# Radarv3.net
KiCad netlist of a schematic drawn in EAGLE
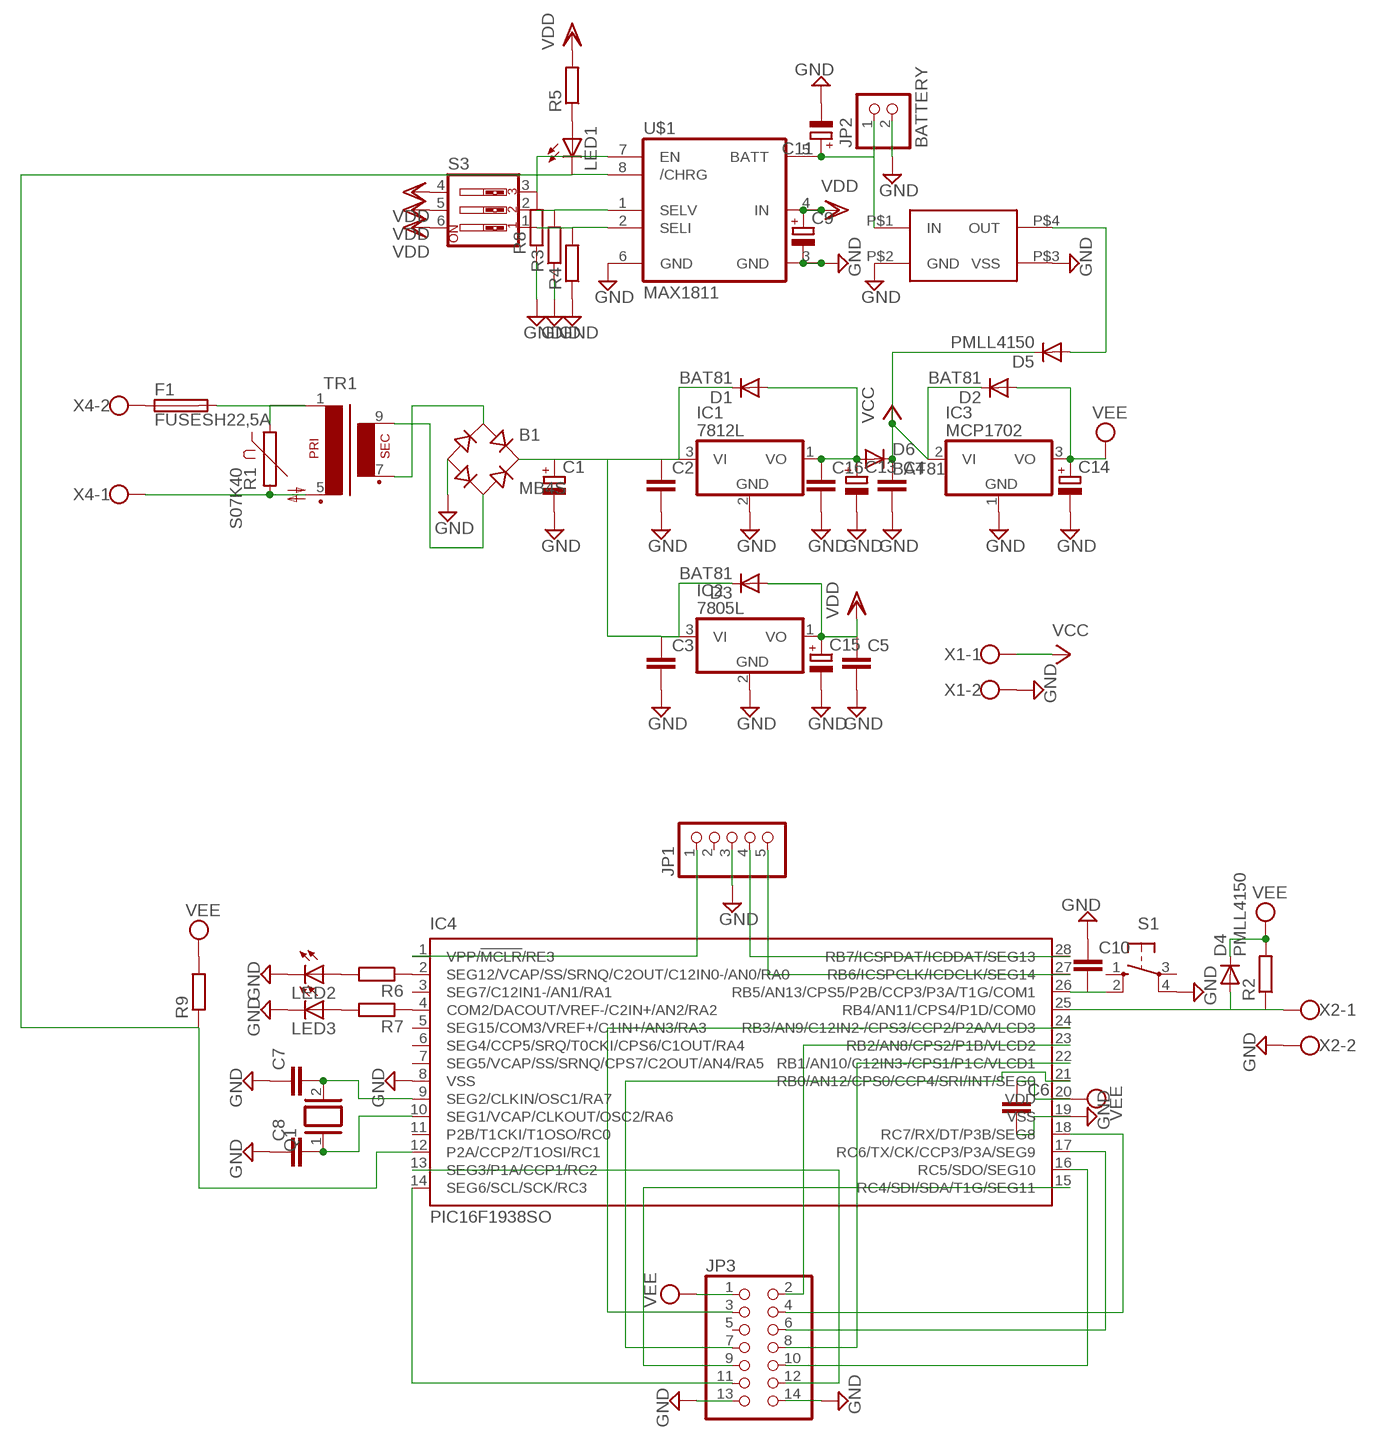
[diagram p0: schematic, sheet 1]

(export (version "E")
  (design (tool "Eeschema 10.0.6"))
  (components
    (comp (ref "B1")
      (value "MB4S")
      (footprint "eagle-import:SOIC-4")
      (libsource (lib "eagle-import") (part "MBS4"))
    )
    (comp (ref "C1")
      (value "CPOL-EUE3.5-10")
      (footprint "eagle-import:E3,5-10")
      (libsource (lib "eagle-import") (part "CPOL-EUE3.5-10"))
    )
    (comp (ref "C2")
      (value "C-EUC1206")
      (footprint "eagle-import:C1206")
      (libsource (lib "eagle-import") (part "resistor_C-EUC1206"))
    )
    (comp (ref "C3")
      (value "C-EUC1206")
      (footprint "eagle-import:C1206")
      (libsource (lib "eagle-import") (part "resistor_C-EUC1206"))
    )
    (comp (ref "C4")
      (value "C-EUC1206")
      (footprint "eagle-import:C1206")
      (libsource (lib "eagle-import") (part "resistor_C-EUC1206"))
    )
    (comp (ref "C5")
      (value "C-EUC1206")
      (footprint "eagle-import:C1206")
      (libsource (lib "eagle-import") (part "resistor_C-EUC1206"))
    )
    (comp (ref "C6")
      (value "C-EU025-030X050")
      (footprint "eagle-import:C025-030X050")
      (libsource (lib "eagle-import") (part "C-EU025-030X050"))
    )
    (comp (ref "C7")
      (value "C-EUC1206")
      (footprint "eagle-import:C1206")
      (libsource (lib "eagle-import") (part "resistor_C-EUC1206"))
    )
    (comp (ref "C8")
      (value "C-EUC1206")
      (footprint "eagle-import:C1206")
      (libsource (lib "eagle-import") (part "resistor_C-EUC1206"))
    )
    (comp (ref "C9")
      (value "CPOL-EUE2,5-6E")
      (footprint "eagle-import:E2,5-6E")
      (libsource (lib "eagle-import") (part "CPOL-EUE2,5-6E"))
    )
    (comp (ref "C10")
      (value "C-EUC1206")
      (footprint "eagle-import:C1206")
      (libsource (lib "eagle-import") (part "resistor_C-EUC1206"))
    )
    (comp (ref "C11")
      (value "CPOL-EUE2,5-6E")
      (footprint "eagle-import:E2,5-6E")
      (libsource (lib "eagle-import") (part "CPOL-EUE2,5-6E"))
    )
    (comp (ref "C13")
      (value "CPOL-EUE2,5-6E")
      (footprint "eagle-import:E2,5-6E")
      (libsource (lib "eagle-import") (part "CPOL-EUE2,5-6E"))
    )
    (comp (ref "C14")
      (value "CPOL-EUE2,5-6E")
      (footprint "eagle-import:E2,5-6E")
      (libsource (lib "eagle-import") (part "CPOL-EUE2,5-6E"))
    )
    (comp (ref "C15")
      (value "CPOL-EUE2,5-6E")
      (footprint "eagle-import:E2,5-6E")
      (libsource (lib "eagle-import") (part "CPOL-EUE2,5-6E"))
    )
    (comp (ref "C16")
      (value "C-EUC1206")
      (footprint "eagle-import:C1206")
      (libsource (lib "eagle-import") (part "resistor_C-EUC1206"))
    )
    (comp (ref "D1")
      (value "BAT81")
      (footprint "eagle-import:DO34-7")
      (libsource (lib "eagle-import") (part "BAT81"))
    )
    (comp (ref "D2")
      (value "BAT81")
      (footprint "eagle-import:DO34-7")
      (libsource (lib "eagle-import") (part "BAT81"))
    )
    (comp (ref "D3")
      (value "BAT81")
      (footprint "eagle-import:DO34-7")
      (libsource (lib "eagle-import") (part "BAT81"))
    )
    (comp (ref "D4")
      (value "PMLL4150")
      (footprint "eagle-import:SOD80C")
      (libsource (lib "eagle-import") (part "PMLL4150"))
    )
    (comp (ref "D5")
      (value "PMLL4150")
      (footprint "eagle-import:SOD80C")
      (libsource (lib "eagle-import") (part "PMLL4150"))
    )
    (comp (ref "D6")
      (value "BAT81")
      (footprint "eagle-import:DO34-7")
      (libsource (lib "eagle-import") (part "BAT81"))
    )
    (comp (ref "F1")
      (value "FUSESH22,5A")
      (footprint "eagle-import:SH22,5A")
      (libsource (lib "eagle-import") (part "FUSESH22,5A"))
    )
    (comp (ref "IC1")
      (value "7812L")
      (footprint "eagle-import:TO92")
      (libsource (lib "eagle-import") (part "78L12"))
    )
    (comp (ref "IC2")
      (value "7805L")
      (footprint "eagle-import:TO92")
      (libsource (lib "eagle-import") (part "78L05"))
    )
    (comp (ref "IC3")
      (value "MCP1702")
      (footprint "eagle-import:TO-92")
      (libsource (lib "eagle-import") (part "MCP1702"))
    )
    (comp (ref "IC4")
      (value "PIC16F1938SO")
      (footprint "eagle-import:SO28W")
      (fields (field (name "MPN") "PIC16F1938-I/SO"))
      (libsource (lib "eagle-import") (part "PIC16F19SO38"))
    )
    (comp (ref "JP1")
      (value "PINHD-1X5")
      (footprint "eagle-import:1X05")
      (libsource (lib "eagle-import") (part "PINHD-1X5"))
    )
    (comp (ref "JP2")
      (value "BATTERY")
      (footprint "eagle-import:1X02")
      (libsource (lib "eagle-import") (part "PINHD-1X2"))
    )
    (comp (ref "JP3")
      (value "PINHD-2X7")
      (footprint "eagle-import:2X07")
      (libsource (lib "eagle-import") (part "PINHD-2X7"))
    )
    (comp (ref "LED1")
      (value "LED3MM")
      (footprint "eagle-import:LED3MM")
      (libsource (lib "eagle-import") (part "LED3MM"))
    )
    (comp (ref "LED2")
      (value "LED3MM")
      (footprint "eagle-import:LED3MM")
      (libsource (lib "eagle-import") (part "LED3MM"))
    )
    (comp (ref "LED3")
      (value "LED3MM")
      (footprint "eagle-import:LED3MM")
      (libsource (lib "eagle-import") (part "LED3MM"))
    )
    (comp (ref "Q1")
      (value "XTAL/S")
      (footprint "eagle-import:QS")
      (libsource (lib "eagle-import") (part "XTAL/S"))
    )
    (comp (ref "R1")
      (value "S07K40")
      (footprint "eagle-import:S07K40")
      (libsource (lib "eagle-import") (part "S07K40"))
    )
    (comp (ref "R2")
      (value "R-EU_M1206")
      (footprint "eagle-import:M1206")
      (libsource (lib "eagle-import") (part "R-EU_M1206"))
    )
    (comp (ref "R3")
      (value "R-EU_M1206")
      (footprint "eagle-import:M1206")
      (libsource (lib "eagle-import") (part "R-EU_M1206"))
    )
    (comp (ref "R4")
      (value "R-EU_M1206")
      (footprint "eagle-import:M1206")
      (libsource (lib "eagle-import") (part "R-EU_M1206"))
    )
    (comp (ref "R5")
      (value "R-EU_M1206")
      (footprint "eagle-import:M1206")
      (libsource (lib "eagle-import") (part "R-EU_M1206"))
    )
    (comp (ref "R6")
      (value "R-EU_M1206")
      (footprint "eagle-import:M1206")
      (libsource (lib "eagle-import") (part "R-EU_M1206"))
    )
    (comp (ref "R7")
      (value "R-EU_M1206")
      (footprint "eagle-import:M1206")
      (libsource (lib "eagle-import") (part "R-EU_M1206"))
    )
    (comp (ref "R8")
      (value "R-EU_M1206")
      (footprint "eagle-import:M1206")
      (libsource (lib "eagle-import") (part "R-EU_M1206"))
    )
    (comp (ref "R9")
      (value "R-EU_M1206")
      (footprint "eagle-import:M1206")
      (libsource (lib "eagle-import") (part "R-EU_M1206"))
    )
    (comp (ref "S1")
      (value "10-XX")
      (footprint "eagle-import:B3F-10XX")
      (fields (field (name "MPN") "B3F-1000"))
      (libsource (lib "eagle-import") (part "10-XX"))
    )
    (comp (ref "S3")
      (value "SW_DIP-3")
      (footprint "eagle-import:EDG-03")
      (libsource (lib "eagle-import") (part "SW_DIP-3"))
    )
    (comp (ref "TR1")
      (value "VV11")
      (footprint "eagle-import:VV11")
      (libsource (lib "eagle-import") (part "VV11"))
    )
    (comp (ref "U$1")
      (value "MAX1811")
      (footprint "eagle-import:SO08")
      (libsource (lib "eagle-import") (part "MAX1811"))
    )
    (comp (ref "U$2")
      (value "STEP_UP_MODULE")
      (footprint "eagle-import:STEP_UP_MOD")
      (libsource (lib "eagle-import") (part "STEP_UP_MODULE"))
    )
    (comp (ref "X1")
      (value "W237-102")
      (footprint "eagle-import:W237-102")
      (fields
        (field (name "MPN") "237-102")
        (field (name "MPN_1") "237-102")
        (field (name "OC_FARNELL") "unknown")
        (field (name "OC_NEWARK") "70K9898")
      )
      (libsource (lib "eagle-import") (part "W237-102"))
    )
    (comp (ref "X2")
      (value "W237-102")
      (footprint "eagle-import:W237-102")
      (fields
        (field (name "MPN") "237-102")
        (field (name "MPN_1") "237-102")
        (field (name "OC_FARNELL") "unknown")
        (field (name "OC_NEWARK") "70K9898")
      )
      (libsource (lib "eagle-import") (part "W237-102"))
    )
    (comp (ref "X4")
      (value "W237-102")
      (footprint "eagle-import:W237-102")
      (fields
        (field (name "MPN") "237-102")
        (field (name "MPN_1") "237-102")
        (field (name "OC_FARNELL") "unknown")
        (field (name "OC_NEWARK") "70K9898")
      )
      (libsource (lib "eagle-import") (part "W237-102"))
    )
  )
  (nets
    (net (code "1") (name "GND") (class "Default")
      (node (ref "B1") (pin "-") (pinfunction "-_-") (pintype "passive"))
      (node (ref "C1") (pin "-") (pinfunction "-_-") (pintype "passive"))
      (node (ref "C10") (pin "1") (pinfunction "1_1") (pintype "passive"))
      (node (ref "C11") (pin "-") (pinfunction "-_-") (pintype "passive"))
      (node (ref "C13") (pin "-") (pinfunction "-_-") (pintype "passive"))
      (node (ref "C14") (pin "-") (pinfunction "-_-") (pintype "passive"))
      (node (ref "C15") (pin "-") (pinfunction "-_-") (pintype "passive"))
      (node (ref "C16") (pin "2") (pinfunction "2_2") (pintype "passive"))
      (node (ref "C2") (pin "2") (pinfunction "2_2") (pintype "passive"))
      (node (ref "C3") (pin "2") (pinfunction "2_2") (pintype "passive"))
      (node (ref "C4") (pin "2") (pinfunction "2_2") (pintype "passive"))
      (node (ref "C5") (pin "2") (pinfunction "2_2") (pintype "passive"))
      (node (ref "C6") (pin "2") (pinfunction "2_2") (pintype "passive"))
      (node (ref "C7") (pin "1") (pinfunction "1_1") (pintype "passive"))
      (node (ref "C8") (pin "1") (pinfunction "1_1") (pintype "passive"))
      (node (ref "C9") (pin "-") (pinfunction "-_-") (pintype "passive"))
      (node (ref "IC1") (pin "2") (pinfunction "GND_2") (pintype "passive"))
      (node (ref "IC2") (pin "2") (pinfunction "GND_2") (pintype "passive"))
      (node (ref "IC3") (pin "1") (pinfunction "GND_1") (pintype "passive"))
      (node (ref "IC4") (pin "19") (pinfunction "VSS_19") (pintype "power_in"))
      (node (ref "IC4") (pin "8") (pinfunction "VSS_8") (pintype "power_in"))
      (node (ref "JP1") (pin "3") (pinfunction "3_3") (pintype "passive"))
      (node (ref "JP2") (pin "2") (pinfunction "2_2") (pintype "passive"))
      (node (ref "JP3") (pin "13") (pinfunction "13_13") (pintype "passive"))
      (node (ref "JP3") (pin "14") (pinfunction "14_14") (pintype "passive"))
      (node (ref "LED2") (pin "K") (pinfunction "C_K") (pintype "passive"))
      (node (ref "LED3") (pin "K") (pinfunction "C_K") (pintype "passive"))
      (node (ref "R3") (pin "1") (pinfunction "1_1") (pintype "passive"))
      (node (ref "R4") (pin "1") (pinfunction "1_1") (pintype "passive"))
      (node (ref "R8") (pin "1") (pinfunction "1_1") (pintype "passive"))
      (node (ref "S1") (pin "4") (pinfunction "P1_4") (pintype "passive"))
      (node (ref "U$1") (pin "3") (pinfunction "GND_3") (pintype "power_in"))
      (node (ref "U$1") (pin "6") (pinfunction "GND_6") (pintype "power_in"))
      (node (ref "U$2") (pin "P$2") (pinfunction "GND_P$2") (pintype "bidirectional"))
      (node (ref "U$2") (pin "P$3") (pinfunction "VSS_P$3") (pintype "bidirectional"))
      (node (ref "X1") (pin "2") (pinfunction "KL_2") (pintype "passive"))
      (node (ref "X2") (pin "2") (pinfunction "KL_2") (pintype "passive"))
    )
    (net (code "2") (name "Net-(B1-AC1)") (class "Default")
      (node (ref "B1") (pin "~1") (pinfunction "AC1_~1") (pintype "passive"))
      (node (ref "TR1") (pin "7") (pinfunction "S3_7") (pintype "passive"))
    )
    (net (code "3") (name "Net-(B1-AC2)") (class "Default")
      (node (ref "B1") (pin "~2") (pinfunction "AC2_~2") (pintype "passive"))
      (node (ref "TR1") (pin "9") (pinfunction "S4_9") (pintype "passive"))
    )
    (net (code "4") (name "Net-(IC1-VI)") (class "Default")
      (node (ref "B1") (pin "+") (pinfunction "+_+") (pintype "passive"))
      (node (ref "C1") (pin "+") (pinfunction "+_+") (pintype "passive"))
      (node (ref "C2") (pin "1") (pinfunction "1_1") (pintype "passive"))
      (node (ref "C3") (pin "1") (pinfunction "1_1") (pintype "passive"))
      (node (ref "D1") (pin "C") (pinfunction "C_C") (pintype "passive"))
      (node (ref "D3") (pin "C") (pinfunction "C_C") (pintype "passive"))
      (node (ref "IC1") (pin "3") (pinfunction "VI_3") (pintype "input"))
      (node (ref "IC2") (pin "3") (pinfunction "VI_3") (pintype "input"))
    )
    (net (code "5") (name "Net-(IC1-VO)") (class "Default")
      (node (ref "C13") (pin "+") (pinfunction "+_+") (pintype "passive"))
      (node (ref "C16") (pin "1") (pinfunction "1_1") (pintype "passive"))
      (node (ref "D1") (pin "A") (pinfunction "A_A") (pintype "passive"))
      (node (ref "D6") (pin "A") (pinfunction "A_A") (pintype "passive"))
      (node (ref "IC1") (pin "1") (pinfunction "VO_1") (pintype "passive"))
    )
    (net (code "6") (name "Net-(IC4-COM2{slash}DACOUT{slash}VREF-{slash}C2IN+{slash}AN2{slash}RA2)") (class "Default")
      (node (ref "IC4") (pin "4") (pinfunction "COM2/DACOUT/VREF-/C2IN+/AN2/RA2_4") (pintype "bidirectional"))
      (node (ref "R7") (pin "1") (pinfunction "1_1") (pintype "passive"))
    )
    (net (code "7") (name "Net-(IC4-P2A{slash}CCP2{slash}T1OSI{slash}RC1)") (class "Default")
      (node (ref "IC4") (pin "12") (pinfunction "P2A/CCP2/T1OSI/RC1_12") (pintype "bidirectional"))
      (node (ref "LED1") (pin "K") (pinfunction "C_K") (pintype "passive"))
      (node (ref "R9") (pin "1") (pinfunction "1_1") (pintype "passive"))
      (node (ref "U$1") (pin "8") (pinfunction "/CHRG_8") (pintype "output"))
    )
    (net (code "8") (name "Net-(IC4-RB0{slash}AN12{slash}CPS0{slash}CCP4{slash}SRI{slash}INT{slash}SEG0)") (class "Default")
      (node (ref "IC4") (pin "21") (pinfunction "RB0/AN12/CPS0/CCP4/SRI/INT/SEG0_21") (pintype "bidirectional"))
      (node (ref "JP3") (pin "7") (pinfunction "7_7") (pintype "passive"))
    )
    (net (code "9") (name "Net-(IC4-RB1{slash}AN10{slash}C12IN3-{slash}CPS1{slash}P1C{slash}VLCD1)") (class "Default")
      (node (ref "IC4") (pin "22") (pinfunction "RB1/AN10/C12IN3-/CPS1/P1C/VLCD1_22") (pintype "bidirectional"))
      (node (ref "JP3") (pin "8") (pinfunction "8_8") (pintype "passive"))
    )
    (net (code "10") (name "Net-(IC4-RB2{slash}AN8{slash}CPS2{slash}P1B{slash}VLCD2)") (class "Default")
      (node (ref "IC4") (pin "23") (pinfunction "RB2/AN8/CPS2/P1B/VLCD2_23") (pintype "bidirectional"))
      (node (ref "JP3") (pin "2") (pinfunction "2_2") (pintype "passive"))
    )
    (net (code "11") (name "Net-(IC4-RB3{slash}AN9{slash}C12IN2-{slash}CPS3{slash}CCP2{slash}P2A{slash}VLCD3)") (class "Default")
      (node (ref "IC4") (pin "24") (pinfunction "RB3/AN9/C12IN2-/CPS3/CCP2/P2A/VLCD3_24") (pintype "bidirectional"))
      (node (ref "JP3") (pin "3") (pinfunction "3_3") (pintype "passive"))
    )
    (net (code "12") (name "Net-(IC4-RB4{slash}AN11{slash}CPS4{slash}P1D{slash}COM0)") (class "Default")
      (node (ref "D4") (pin "A") (pinfunction "A_A") (pintype "passive"))
      (node (ref "IC4") (pin "25") (pinfunction "RB4/AN11/CPS4/P1D/COM0_25") (pintype "bidirectional"))
      (node (ref "R2") (pin "1") (pinfunction "1_1") (pintype "passive"))
      (node (ref "X2") (pin "1") (pinfunction "KL_1") (pintype "passive"))
    )
    (net (code "13") (name "Net-(IC4-RB5{slash}AN13{slash}CPS5{slash}P2B{slash}CCP3{slash}P3A{slash}T1G{slash}COM1)") (class "Default")
      (node (ref "C10") (pin "2") (pinfunction "2_2") (pintype "passive"))
      (node (ref "IC4") (pin "26") (pinfunction "RB5/AN13/CPS5/P2B/CCP3/P3A/T1G/COM1_26") (pintype "bidirectional"))
      (node (ref "S1") (pin "2") (pinfunction "S1_2") (pintype "passive"))
    )
    (net (code "14") (name "Net-(IC4-RB6{slash}ICSPCLK{slash}ICDCLK{slash}SEG14)") (class "Default")
      (node (ref "IC4") (pin "27") (pinfunction "RB6/ICSPCLK/ICDCLK/SEG14_27") (pintype "bidirectional"))
      (node (ref "JP1") (pin "5") (pinfunction "5_5") (pintype "passive"))
    )
    (net (code "15") (name "Net-(IC4-RB7{slash}ICSPDAT{slash}ICDDAT{slash}SEG13)") (class "Default")
      (node (ref "IC4") (pin "28") (pinfunction "RB7/ICSPDAT/ICDDAT/SEG13_28") (pintype "bidirectional"))
      (node (ref "JP1") (pin "4") (pinfunction "4_4") (pintype "passive"))
    )
    (net (code "16") (name "Net-(IC4-RC4{slash}SDI{slash}SDA{slash}T1G{slash}SEG11)") (class "Default")
      (node (ref "IC4") (pin "15") (pinfunction "RC4/SDI/SDA/T1G/SEG11_15") (pintype "bidirectional"))
      (node (ref "JP3") (pin "9") (pinfunction "9_9") (pintype "passive"))
    )
    (net (code "17") (name "Net-(IC4-RC5{slash}SDO{slash}SEG10)") (class "Default")
      (node (ref "IC4") (pin "16") (pinfunction "RC5/SDO/SEG10_16") (pintype "bidirectional"))
      (node (ref "JP3") (pin "10") (pinfunction "10_10") (pintype "passive"))
    )
    (net (code "18") (name "Net-(IC4-RC6{slash}TX{slash}CK{slash}CCP3{slash}P3A{slash}SEG9)") (class "Default")
      (node (ref "IC4") (pin "17") (pinfunction "RC6/TX/CK/CCP3/P3A/SEG9_17") (pintype "bidirectional"))
      (node (ref "JP3") (pin "6") (pinfunction "6_6") (pintype "passive"))
    )
    (net (code "19") (name "Net-(IC4-RC7{slash}RX{slash}DT{slash}P3B{slash}SEG8)") (class "Default")
      (node (ref "IC4") (pin "18") (pinfunction "RC7/RX/DT/P3B/SEG8_18") (pintype "bidirectional"))
      (node (ref "JP3") (pin "4") (pinfunction "4_4") (pintype "passive"))
    )
    (net (code "20") (name "Net-(IC4-SEG1{slash}VCAP{slash}CLKOUT{slash}OSC2{slash}RA6)") (class "Default")
      (node (ref "C8") (pin "2") (pinfunction "2_2") (pintype "passive"))
      (node (ref "IC4") (pin "10") (pinfunction "SEG1/VCAP/CLKOUT/OSC2/RA6_10") (pintype "bidirectional"))
      (node (ref "Q1") (pin "1") (pinfunction "1_1") (pintype "passive"))
    )
    (net (code "21") (name "Net-(IC4-SEG2{slash}CLKIN{slash}OSC1{slash}RA7)") (class "Default")
      (node (ref "C7") (pin "2") (pinfunction "2_2") (pintype "passive"))
      (node (ref "IC4") (pin "9") (pinfunction "SEG2/CLKIN/OSC1/RA7_9") (pintype "bidirectional"))
      (node (ref "Q1") (pin "2") (pinfunction "2_2") (pintype "passive"))
    )
    (net (code "22") (name "Net-(IC4-SEG3{slash}P1A{slash}CCP1{slash}RC2)") (class "Default")
      (node (ref "IC4") (pin "13") (pinfunction "SEG3/P1A/CCP1/RC2_13") (pintype "bidirectional"))
      (node (ref "JP3") (pin "12") (pinfunction "12_12") (pintype "passive"))
    )
    (net (code "23") (name "Net-(IC4-SEG6{slash}SCL{slash}SCK{slash}RC3)") (class "Default")
      (node (ref "IC4") (pin "14") (pinfunction "SEG6/SCL/SCK/RC3_14") (pintype "bidirectional"))
      (node (ref "JP3") (pin "11") (pinfunction "11_11") (pintype "passive"))
    )
    (net (code "24") (name "Net-(IC4-SEG12{slash}VCAP{slash}SS{slash}SRNQ{slash}C2OUT{slash}C12IN0-{slash}AN0{slash}RA0)") (class "Default")
      (node (ref "IC4") (pin "2") (pinfunction "SEG12/VCAP/SS/SRNQ/C2OUT/C12IN0-/AN0/RA0_2") (pintype "bidirectional"))
      (node (ref "R6") (pin "1") (pinfunction "1_1") (pintype "passive"))
    )
    (net (code "25") (name "Net-(IC4-VPP{slash}~{MCLR}{slash}RE3)") (class "Default")
      (node (ref "IC4") (pin "1") (pinfunction "VPP/~{MCLR}/RE3_1") (pintype "input"))
      (node (ref "JP1") (pin "1") (pinfunction "1_1") (pintype "passive"))
    )
    (net (code "26") (name "Net-(LED1-PadA)") (class "Default")
      (node (ref "LED1") (pin "A") (pinfunction "A_A") (pintype "passive"))
      (node (ref "R5") (pin "1") (pinfunction "1_1") (pintype "passive"))
    )
    (net (code "27") (name "Net-(LED2-PadA)") (class "Default")
      (node (ref "LED2") (pin "A") (pinfunction "A_A") (pintype "passive"))
      (node (ref "R6") (pin "2") (pinfunction "2_2") (pintype "passive"))
    )
    (net (code "28") (name "Net-(LED3-PadA)") (class "Default")
      (node (ref "LED3") (pin "A") (pinfunction "A_A") (pintype "passive"))
      (node (ref "R7") (pin "2") (pinfunction "2_2") (pintype "passive"))
    )
    (net (code "29") (name "Net-(TR1-P1)") (class "Default")
      (node (ref "F1") (pin "2") (pinfunction "2_2") (pintype "passive"))
      (node (ref "R1") (pin "1") (pinfunction "1_1") (pintype "passive"))
      (node (ref "TR1") (pin "1") (pinfunction "P1_1") (pintype "passive"))
    )
    (net (code "30") (name "Net-(TR1-P2)") (class "Default")
      (node (ref "R1") (pin "2") (pinfunction "2_2") (pintype "passive"))
      (node (ref "TR1") (pin "5") (pinfunction "P2_5") (pintype "passive"))
      (node (ref "X4") (pin "1") (pinfunction "KL_1") (pintype "passive"))
    )
    (net (code "31") (name "Net-(U$1-BATT)") (class "Default")
      (node (ref "C11") (pin "+") (pinfunction "+_+") (pintype "passive"))
      (node (ref "JP2") (pin "1") (pinfunction "1_1") (pintype "passive"))
      (node (ref "U$1") (pin "5") (pinfunction "BATT_5") (pintype "output"))
      (node (ref "U$2") (pin "P$1") (pinfunction "IN_P$1") (pintype "bidirectional"))
    )
    (net (code "32") (name "Net-(U$1-EN)") (class "Default")
      (node (ref "R8") (pin "2") (pinfunction "2_2") (pintype "passive"))
      (node (ref "S3") (pin "3") (pinfunction "3_3") (pintype "passive"))
      (node (ref "U$1") (pin "7") (pinfunction "EN_7") (pintype "input"))
    )
    (net (code "33") (name "Net-(U$1-SELI)") (class "Default")
      (node (ref "R4") (pin "2") (pinfunction "2_2") (pintype "passive"))
      (node (ref "S3") (pin "1") (pinfunction "1_1") (pintype "passive"))
      (node (ref "U$1") (pin "2") (pinfunction "SELI_2") (pintype "input"))
    )
    (net (code "34") (name "Net-(U$1-SELV)") (class "Default")
      (node (ref "R3") (pin "2") (pinfunction "2_2") (pintype "passive"))
      (node (ref "S3") (pin "2") (pinfunction "2_2") (pintype "passive"))
      (node (ref "U$1") (pin "1") (pinfunction "SELV_1") (pintype "input"))
    )
    (net (code "35") (name "Net-(U$2-OUT)") (class "Default")
      (node (ref "D5") (pin "A") (pinfunction "A_A") (pintype "passive"))
      (node (ref "U$2") (pin "P$4") (pinfunction "OUT_P$4") (pintype "bidirectional"))
    )
    (net (code "36") (name "Net-(X4B-KL)") (class "Default")
      (node (ref "F1") (pin "1") (pinfunction "1_1") (pintype "passive"))
      (node (ref "X4") (pin "2") (pinfunction "KL_2") (pintype "passive"))
    )
    (net (code "37") (name "VCC") (class "Default")
      (node (ref "C4") (pin "1") (pinfunction "1_1") (pintype "passive"))
      (node (ref "D2") (pin "C") (pinfunction "C_C") (pintype "passive"))
      (node (ref "D5") (pin "C") (pinfunction "C_C") (pintype "passive"))
      (node (ref "D6") (pin "C") (pinfunction "C_C") (pintype "passive"))
      (node (ref "IC3") (pin "2") (pinfunction "VI_2") (pintype "input"))
      (node (ref "X1") (pin "1") (pinfunction "KL_1") (pintype "passive"))
    )
    (net (code "38") (name "VDD") (class "Default")
      (node (ref "C15") (pin "+") (pinfunction "+_+") (pintype "passive"))
      (node (ref "C5") (pin "1") (pinfunction "1_1") (pintype "passive"))
      (node (ref "C9") (pin "+") (pinfunction "+_+") (pintype "passive"))
      (node (ref "D3") (pin "A") (pinfunction "A_A") (pintype "passive"))
      (node (ref "IC2") (pin "1") (pinfunction "VO_1") (pintype "passive"))
      (node (ref "R5") (pin "2") (pinfunction "2_2") (pintype "passive"))
      (node (ref "S3") (pin "4") (pinfunction "4_4") (pintype "passive"))
      (node (ref "S3") (pin "5") (pinfunction "5_5") (pintype "passive"))
      (node (ref "S3") (pin "6") (pinfunction "6_6") (pintype "passive"))
      (node (ref "U$1") (pin "4") (pinfunction "IN_4") (pintype "power_in"))
    )
    (net (code "39") (name "VEE") (class "Default")
      (node (ref "C14") (pin "+") (pinfunction "+_+") (pintype "passive"))
      (node (ref "C6") (pin "1") (pinfunction "1_1") (pintype "passive"))
      (node (ref "D2") (pin "A") (pinfunction "A_A") (pintype "passive"))
      (node (ref "D4") (pin "C") (pinfunction "C_C") (pintype "passive"))
      (node (ref "IC3") (pin "3") (pinfunction "VO_3") (pintype "passive"))
      (node (ref "IC4") (pin "20") (pinfunction "VDD_20") (pintype "power_in"))
      (node (ref "JP3") (pin "1") (pinfunction "1_1") (pintype "passive"))
      (node (ref "R2") (pin "2") (pinfunction "2_2") (pintype "passive"))
      (node (ref "R9") (pin "2") (pinfunction "2_2") (pintype "passive"))
    )
    (net (code "40") (name "unconnected-(IC4-P2B{slash}T1CKI{slash}T1OSO{slash}RC0-Pad11)") (class "Default")
      (node (ref "IC4") (pin "11") (pinfunction "P2B/T1CKI/T1OSO/RC0_11") (pintype "bidirectional"))
    )
    (net (code "41") (name "unconnected-(IC4-SEG4{slash}CCP5{slash}SRQ{slash}T0CKI{slash}CPS6{slash}C1OUT{slash}RA4-Pad6)") (class "Default")
      (node (ref "IC4") (pin "6") (pinfunction "SEG4/CCP5/SRQ/T0CKI/CPS6/C1OUT/RA4_6") (pintype "bidirectional"))
    )
    (net (code "42") (name "unconnected-(IC4-SEG5{slash}VCAP{slash}SS{slash}SRNQ{slash}CPS7{slash}C2OUT{slash}AN4{slash}RA5-Pad7)") (class "Default")
      (node (ref "IC4") (pin "7") (pinfunction "SEG5/VCAP/SS/SRNQ/CPS7/C2OUT/AN4/RA5_7") (pintype "bidirectional"))
    )
    (net (code "43") (name "unconnected-(IC4-SEG7{slash}C12IN1-{slash}AN1{slash}RA1-Pad3)") (class "Default")
      (node (ref "IC4") (pin "3") (pinfunction "SEG7/C12IN1-/AN1/RA1_3") (pintype "bidirectional"))
    )
    (net (code "44") (name "unconnected-(IC4-SEG15{slash}COM3{slash}VREF+{slash}C1IN+{slash}AN3{slash}RA3-Pad5)") (class "Default")
      (node (ref "IC4") (pin "5") (pinfunction "SEG15/COM3/VREF+/C1IN+/AN3/RA3_5") (pintype "bidirectional"))
    )
    (net (code "45") (name "unconnected-(JP1-Pad2)") (class "Default")
      (node (ref "JP1") (pin "2") (pinfunction "2_2") (pintype "passive"))
    )
    (net (code "46") (name "unconnected-(JP3-Pad5)") (class "Default")
      (node (ref "JP3") (pin "5") (pinfunction "5_5") (pintype "passive"))
    )
    (net (code "47") (name "unconnected-(S1-P-Pad3)") (class "Default")
      (node (ref "S1") (pin "3") (pinfunction "P_3") (pintype "passive"))
    )
    (net (code "48") (name "unconnected-(S1-S-Pad1)") (class "Default")
      (node (ref "S1") (pin "1") (pinfunction "S_1") (pintype "passive"))
    )
  )
)
